# airball_sensor_board_v8.net
KiCad netlist of a schematic drawn in EAGLE
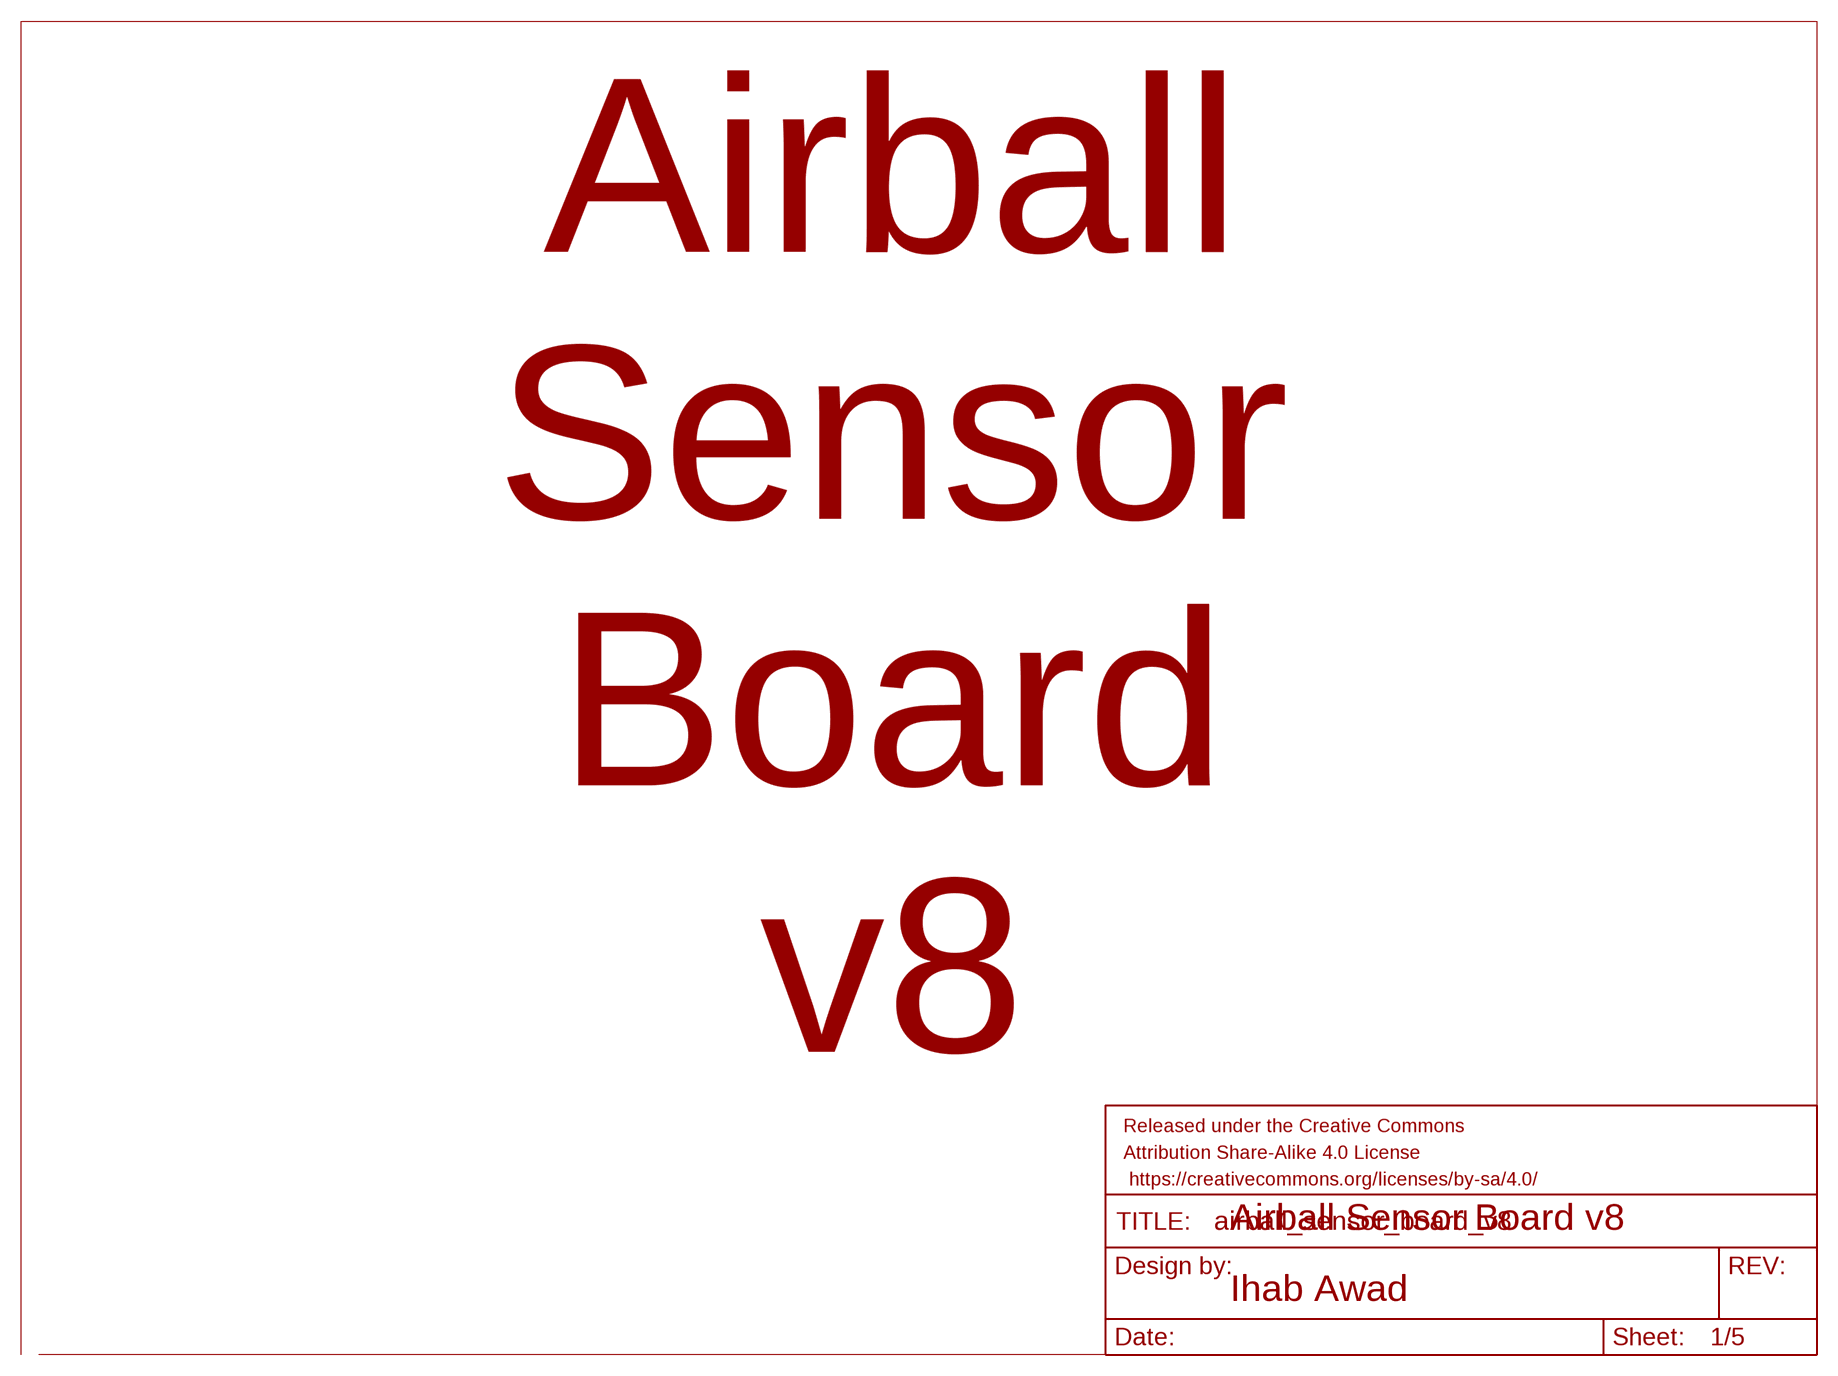
[diagram p0: schematic, sheet 1]
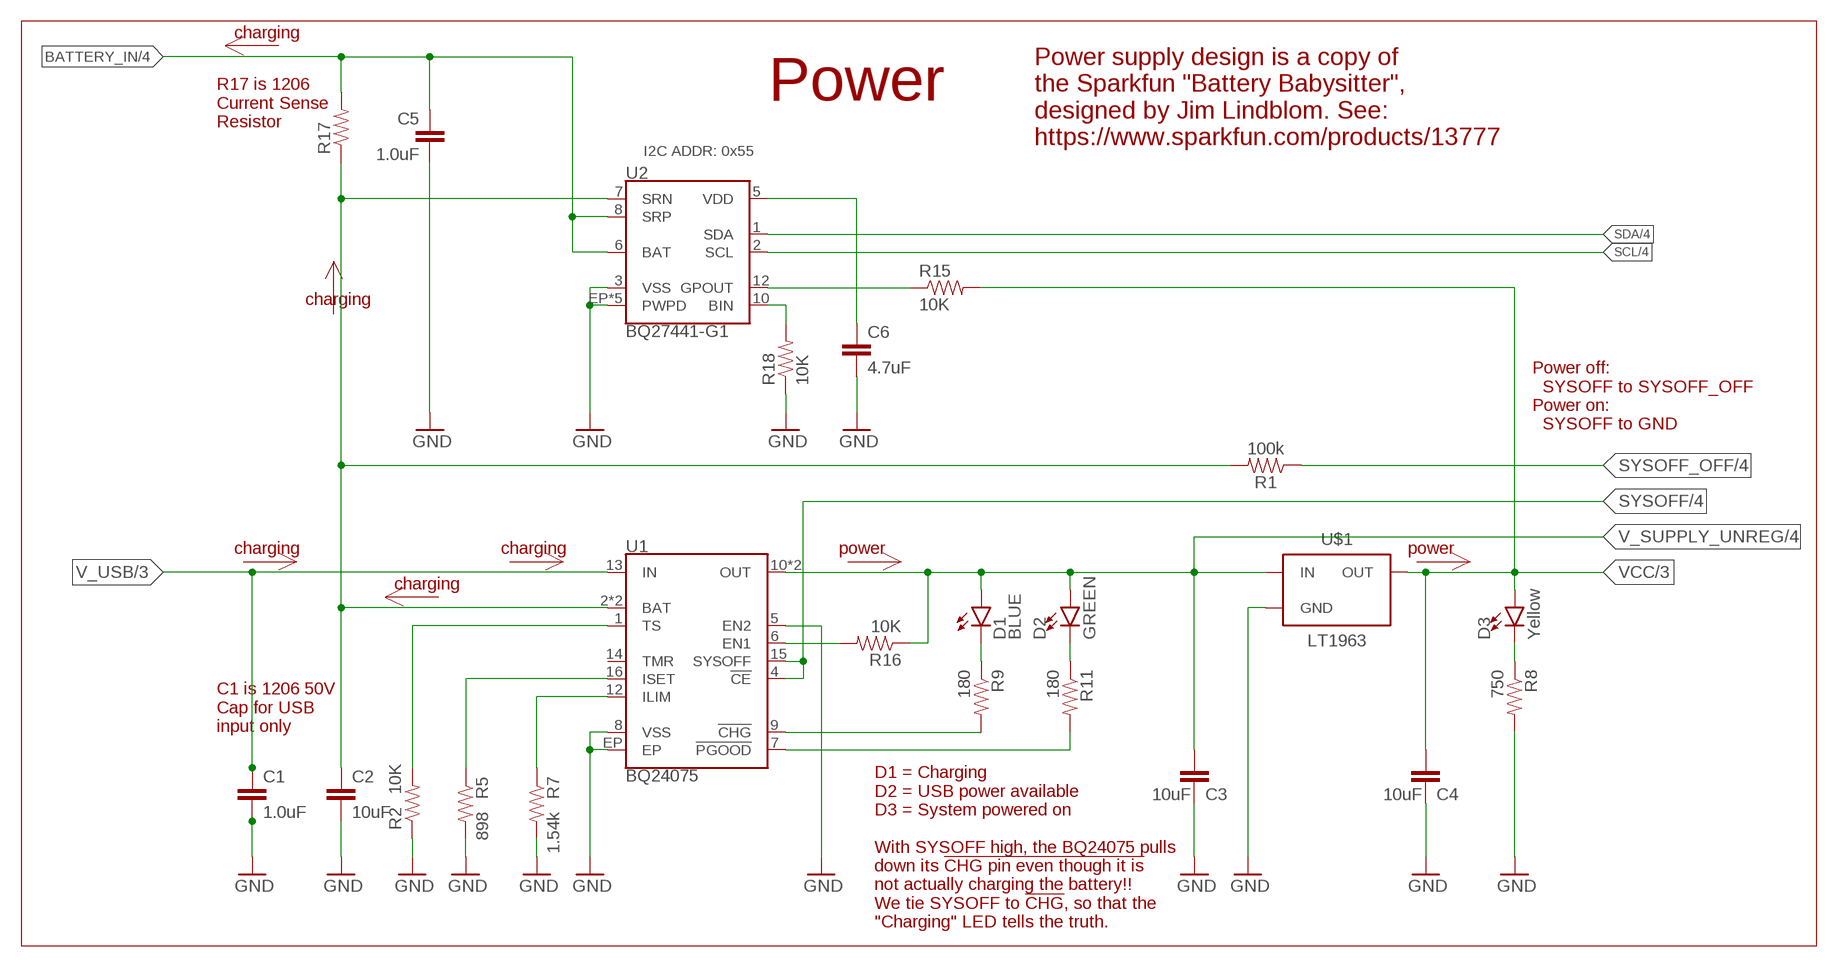
[diagram p1: schematic, sheet 2]
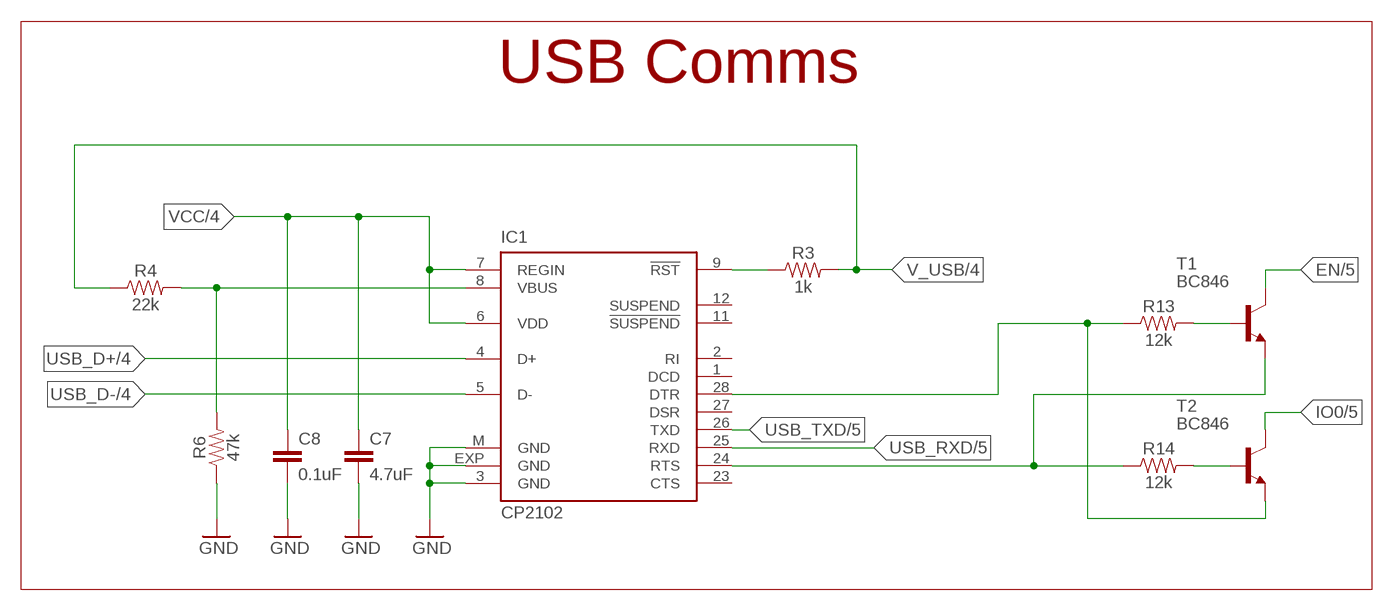
[diagram p2: schematic, sheet 3]
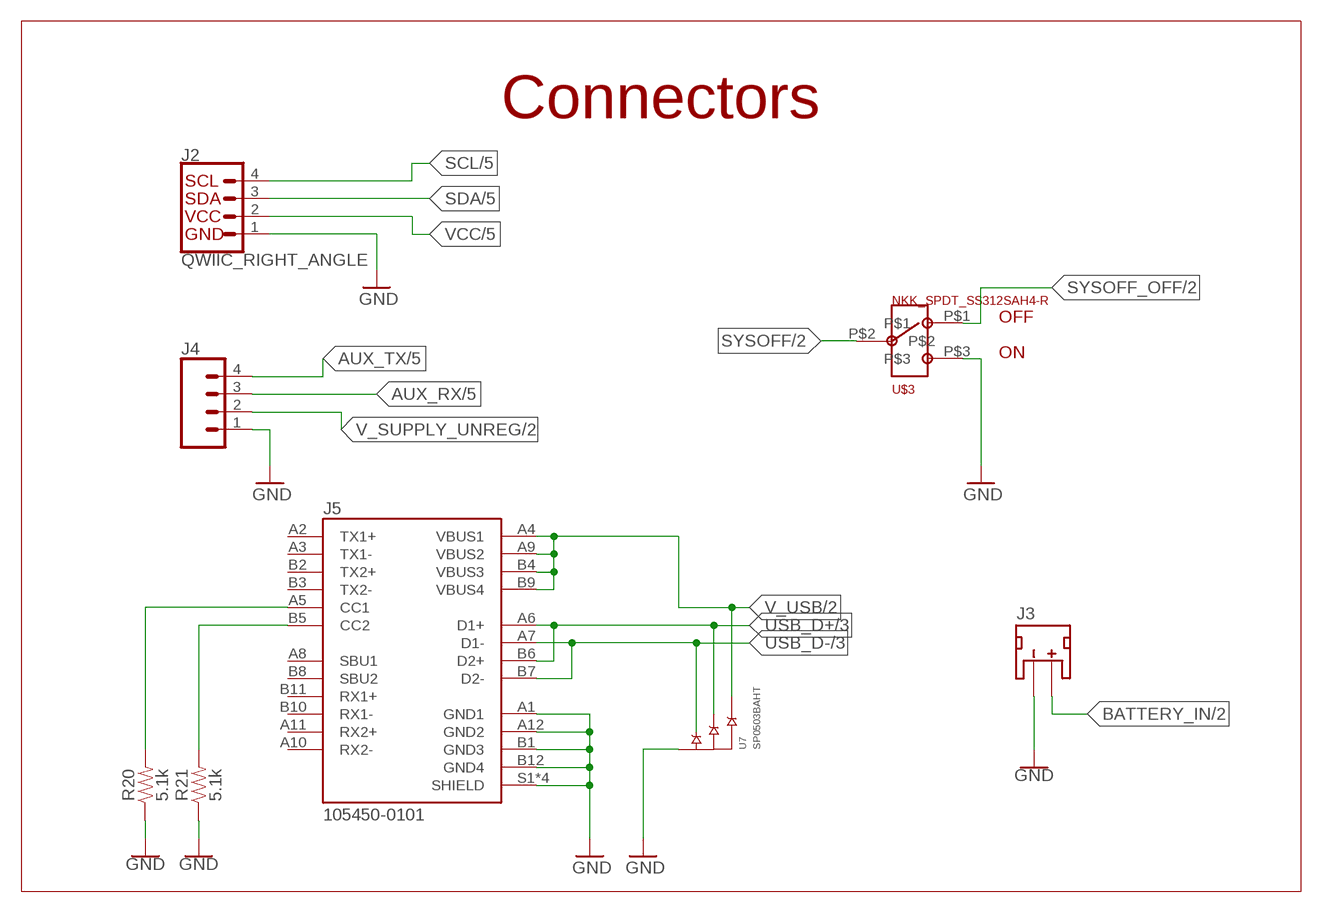
[diagram p3: schematic, sheet 4]
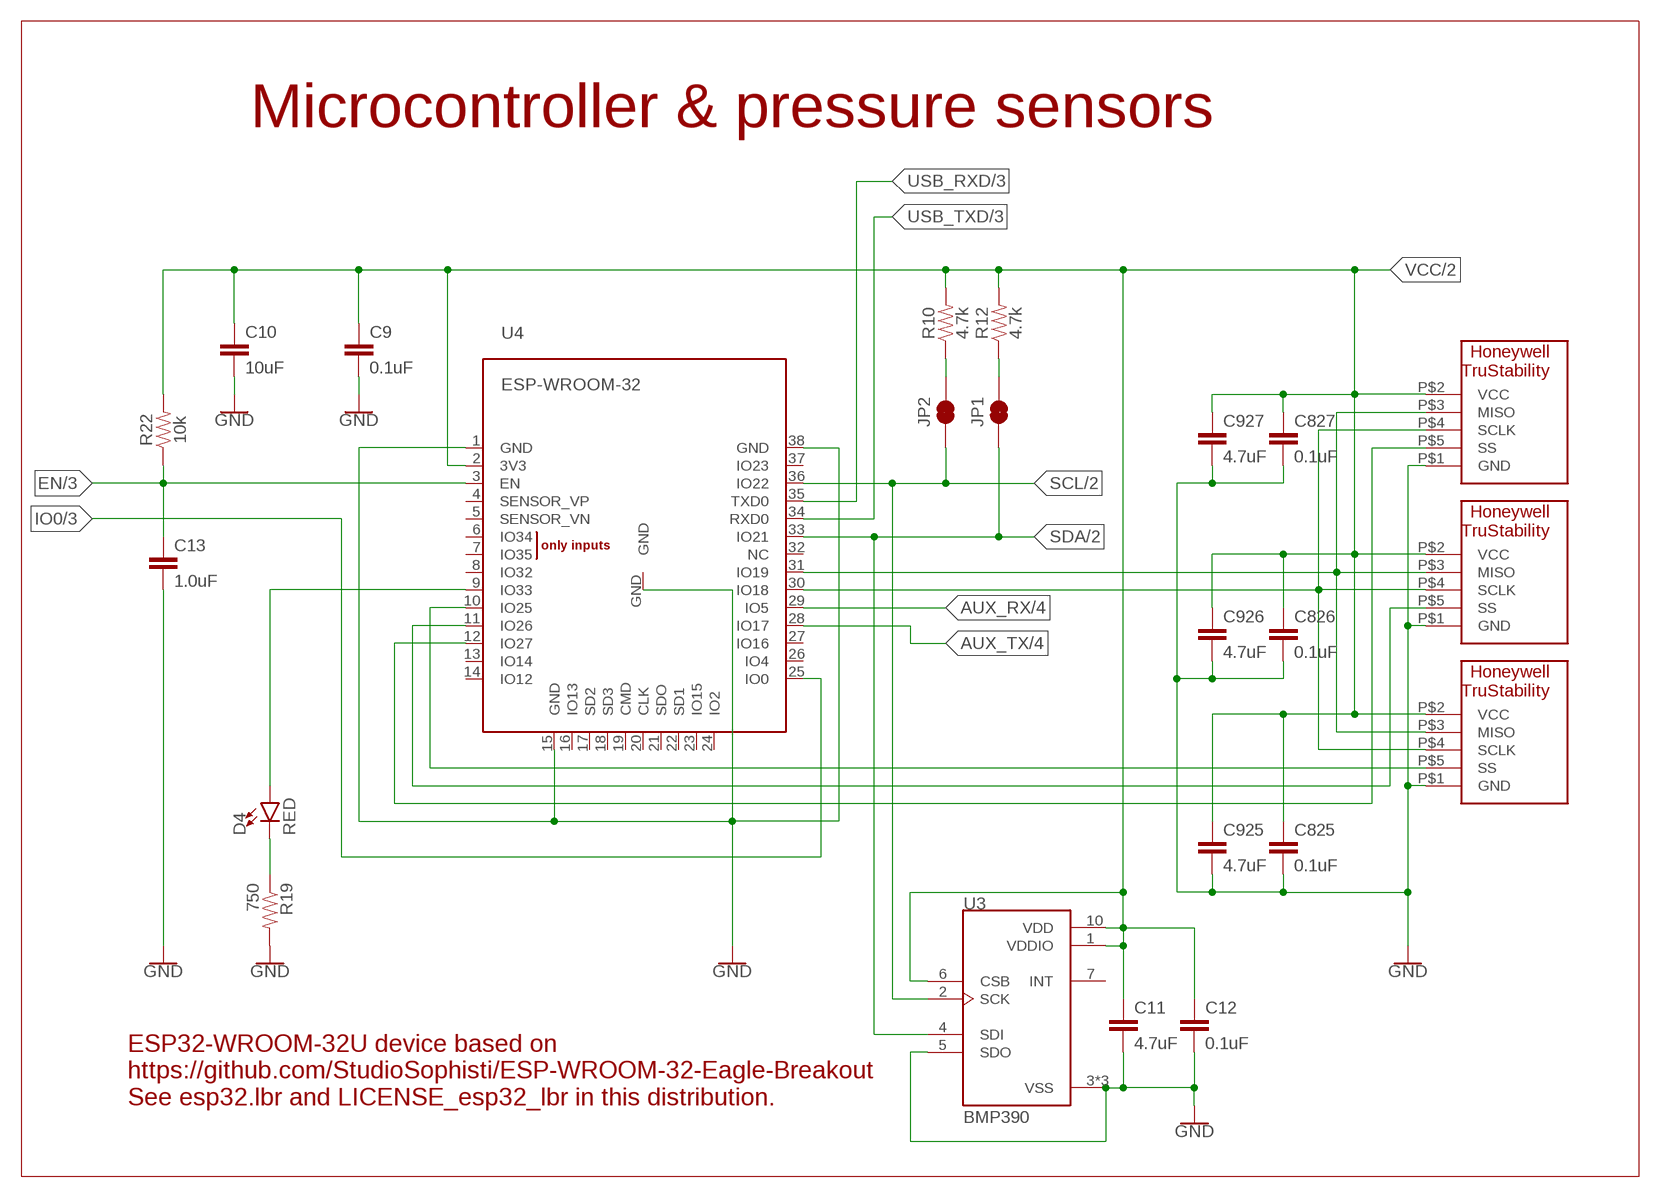
[diagram p4: schematic, sheet 5]

(export (version "E")
  (design (tool "Eeschema 10.0.6"))
  (components
    (comp (ref "C7")
      (value "4.7uF")
      (footprint "eagle-import:0603")
      (libsource (lib "eagle-import") (part "4.7UF-0603-35V-(20%)"))
    )
    (comp (ref "C8")
      (value "0.1uF")
      (footprint "eagle-import:0603")
      (libsource (lib "eagle-import") (part "0.1UF-0603-25V-(+80/-20%)"))
    )
    (comp (ref "IC1")
      (value "CP2102")
      (footprint "eagle-import:MLP28")
      (fields (field (name "MF") "FARNELL") (field (name "MPN") "CP2102-GM"))
      (libsource (lib "eagle-import") (part "CP2102"))
    )
    (comp (ref "R3")
      (value "1k")
      (footprint "eagle-import:0603")
      (libsource (lib "eagle-import") (part "1KOHM-0603-1/10W-1%"))
    )
    (comp (ref "R4")
      (value "22k")
      (footprint "eagle-import:0603")
      (libsource (lib "eagle-import") (part "22KOHM-0603-1/10W-1%"))
    )
    (comp (ref "R6")
      (value "47k")
      (footprint "eagle-import:0603")
      (libsource (lib "eagle-import") (part "47KOHM-0603-1/10W-1%"))
    )
    (comp (ref "R13")
      (value "12k")
      (footprint "eagle-import:0603")
      (libsource (lib "eagle-import") (part "12KOHM-0603-1/10W-1%"))
    )
    (comp (ref "R14")
      (value "12k")
      (footprint "eagle-import:0603")
      (libsource (lib "eagle-import") (part "12KOHM-0603-1/10W-1%"))
    )
    (comp (ref "T1")
      (value "BC846")
      (footprint "eagle-import:SOT23")
      (libsource (lib "eagle-import") (part "BC846"))
    )
    (comp (ref "T2")
      (value "BC846")
      (footprint "eagle-import:SOT23")
      (libsource (lib "eagle-import") (part "BC846"))
    )
    (comp (ref "FRAME1")
      (value "FRAME-LETTER")
      (footprint "eagle-import:CREATIVE_COMMONS")
      (libsource (lib "eagle-import") (part "FRAME-LETTER"))
    )
    (comp (ref "J2")
      (value "QWIIC_RIGHT_ANGLE")
      (footprint "eagle-import:JST04_1MM_RA")
      (libsource (lib "eagle-import") (part "QWIIC_CONNECTORJS-1MM"))
    )
    (comp (ref "J3")
      (value "JST_2MM_MALE")
      (footprint "eagle-import:JST-2-SMD")
      (libsource (lib "eagle-import") (part "JST_2MM_MALE"))
    )
    (comp (ref "J4")
      (value "CONN_04PTH")
      (footprint "eagle-import:1X04")
      (libsource (lib "eagle-import") (part "CONN_04PTH"))
    )
    (comp (ref "J5")
      (value "105450-0101")
      (footprint "eagle-import:MOLEX_105450-0101")
      (fields
        (field (name "DIGI-KEY_PART_NUMBER") "WM12856CT-ND")
        (field (name "MF") "Molex")
        (field (name "MP") "1054500101")
      )
      (libsource (lib "eagle-import") (part "105450-0101"))
    )
    (comp (ref "R20")
      (value "5.1k")
      (footprint "eagle-import:0603")
      (libsource (lib "eagle-import") (part "5.1KOHM5.1KOHM-0603-1/10W-1%"))
    )
    (comp (ref "R21")
      (value "5.1k")
      (footprint "eagle-import:0603")
      (libsource (lib "eagle-import") (part "5.1KOHM5.1KOHM-0603-1/10W-1%"))
    )
    (comp (ref "U$3")
      (value "NKK_SPDT_SS312SAH4-R")
      (footprint "eagle-import:NKK_SPDT_SS312SAH4-R")
      (libsource (lib "eagle-import") (part "NKK_SPDT_SS312SAH4-R"))
    )
    (comp (ref "U7")
      (value "SP0503BAHT")
      (footprint "eagle-import:SOT143")
      (fields (field (name "DIGI-KEY_PART_NUMBER") "F2715TR-ND") (field (name "MF") "Littelfuse Inc."))
      (libsource (lib "eagle-import") (part "SP0503BAHT"))
    )
    (comp (ref "C9")
      (value "0.1uF")
      (footprint "eagle-import:0603")
      (libsource (lib "eagle-import") (part "0.1UF-0603-25V-(+80/-20%)"))
    )
    (comp (ref "C10")
      (value "10uF")
      (footprint "eagle-import:0603")
      (libsource (lib "eagle-import") (part "10UF-0603-6.3V-20%"))
    )
    (comp (ref "C11")
      (value "4.7uF")
      (footprint "eagle-import:0603")
      (libsource (lib "eagle-import") (part "4.7UF-0603-6.3V-(10%)"))
    )
    (comp (ref "C12")
      (value "0.1uF")
      (footprint "eagle-import:0603")
      (libsource (lib "eagle-import") (part "0.1UF-0603-25V-(+80/-20%)"))
    )
    (comp (ref "C13")
      (value "1.0uF")
      (footprint "eagle-import:0603")
      (libsource (lib "eagle-import") (part "1.0UF-0603-16V-10%"))
    )
    (comp (ref "C825")
      (value "0.1uF")
      (footprint "eagle-import:0603")
      (libsource (lib "eagle-import") (part "0.1UF-0603-25V-(+80/-20%)"))
    )
    (comp (ref "C826")
      (value "0.1uF")
      (footprint "eagle-import:0603")
      (libsource (lib "eagle-import") (part "0.1UF-0603-25V-(+80/-20%)"))
    )
    (comp (ref "C827")
      (value "0.1uF")
      (footprint "eagle-import:0603")
      (libsource (lib "eagle-import") (part "0.1UF-0603-25V-(+80/-20%)"))
    )
    (comp (ref "C925")
      (value "4.7uF")
      (footprint "eagle-import:0603")
      (libsource (lib "eagle-import") (part "4.7UF-0603-6.3V-(10%)"))
    )
    (comp (ref "C926")
      (value "4.7uF")
      (footprint "eagle-import:0603")
      (libsource (lib "eagle-import") (part "4.7UF-0603-6.3V-(10%)"))
    )
    (comp (ref "C927")
      (value "4.7uF")
      (footprint "eagle-import:0603")
      (libsource (lib "eagle-import") (part "4.7UF-0603-6.3V-(10%)"))
    )
    (comp (ref "D4")
      (value "RED")
      (footprint "eagle-import:LED-0603")
      (libsource (lib "eagle-import") (part "LED-RED0603"))
    )
    (comp (ref "JP1")
      (value "JUMPER-SMT_2_NC_TRACE_SILK")
      (footprint "eagle-import:SMT-JUMPER_2_NC_TRACE_SILK")
      (libsource (lib "eagle-import") (part "JUMPER-SMT_2_NC_TRACE_SILK"))
    )
    (comp (ref "JP2")
      (value "JUMPER-SMT_2_NC_TRACE_SILK")
      (footprint "eagle-import:SMT-JUMPER_2_NC_TRACE_SILK")
      (libsource (lib "eagle-import") (part "JUMPER-SMT_2_NC_TRACE_SILK"))
    )
    (comp (ref "R10")
      (value "4.7k")
      (footprint "eagle-import:0603")
      (libsource (lib "eagle-import") (part "4.7KOHM-0603-1/10W-1%"))
    )
    (comp (ref "R12")
      (value "4.7k")
      (footprint "eagle-import:0603")
      (libsource (lib "eagle-import") (part "4.7KOHM-0603-1/10W-1%"))
    )
    (comp (ref "R19")
      (value "750")
      (footprint "eagle-import:0603-RES")
      (libsource (lib "eagle-import") (part "10KOHM-1/10W-1%(0603)0603"))
    )
    (comp (ref "R22")
      (value "10k")
      (footprint "eagle-import:0603")
      (libsource (lib "eagle-import") (part "10KOHM-0603-1/10W-1%"))
    )
    (comp (ref "U$925")
      (value "HONEYWELL_HSC_SMT")
      (footprint "eagle-import:HONEYWELL_HSC_SMT")
      (libsource (lib "eagle-import") (part "HONEYWELL_HSC_SMT"))
    )
    (comp (ref "U$926")
      (value "HONEYWELL_HSC_SMT")
      (footprint "eagle-import:HONEYWELL_HSC_SMT")
      (libsource (lib "eagle-import") (part "HONEYWELL_HSC_SMT"))
    )
    (comp (ref "U$927")
      (value "HONEYWELL_HSC_SMT")
      (footprint "eagle-import:HONEYWELL_HSC_SMT")
      (libsource (lib "eagle-import") (part "HONEYWELL_HSC_SMT"))
    )
    (comp (ref "U3")
      (value "BMP390")
      (footprint "eagle-import:PQFN50P200X200X80-10N")
      (fields (field (name "MF") "Bosch Sensortec"))
      (libsource (lib "eagle-import") (part "BMP390"))
    )
    (comp (ref "U4")
      (value "ESP-WROOM-32")
      (footprint "eagle-import:ESP-WROOM-32")
      (libsource (lib "eagle-import") (part "ESP-WROOM-32"))
    )
    (comp (ref "C1")
      (value "1.0uF")
      (footprint "eagle-import:1206-CAP")
      (libsource (lib "eagle-import") (part "1.0UF50V10%(1206)"))
    )
    (comp (ref "C2")
      (value "10uF")
      (footprint "eagle-import:0805-CAP")
      (libsource (lib "eagle-import") (part "10UF10V10%(0805)"))
    )
    (comp (ref "C3")
      (value "10uF")
      (footprint "eagle-import:0805-CAP")
      (libsource (lib "eagle-import") (part "10UF10V10%(0805)"))
    )
    (comp (ref "C4")
      (value "10uF")
      (footprint "eagle-import:0805-CAP")
      (libsource (lib "eagle-import") (part "10UF10V10%(0805)"))
    )
    (comp (ref "C5")
      (value "1.0uF")
      (footprint "eagle-import:0603-CAP")
      (libsource (lib "eagle-import") (part "1.0UF-16V-10%(0603)"))
    )
    (comp (ref "C6")
      (value "4.7uF")
      (footprint "eagle-import:0603")
      (libsource (lib "eagle-import") (part "4.7UF-0603-35V-(20%)"))
    )
    (comp (ref "D1")
      (value "BLUE")
      (footprint "eagle-import:LED-0603")
      (libsource (lib "eagle-import") (part "LED-BLUE0603"))
    )
    (comp (ref "D2")
      (value "GREEN")
      (footprint "eagle-import:LED-0603")
      (libsource (lib "eagle-import") (part "LED-GREEN0603"))
    )
    (comp (ref "D3")
      (value "Yellow")
      (footprint "eagle-import:LED-0603")
      (libsource (lib "eagle-import") (part "LED-YELLOW0603"))
    )
    (comp (ref "R1")
      (value "100k")
      (footprint "eagle-import:0603")
      (libsource (lib "eagle-import") (part "100KOHM-0603-1/10W-1%"))
    )
    (comp (ref "R2")
      (value "10K")
      (footprint "eagle-import:0603-RES")
      (libsource (lib "eagle-import") (part "10KOHM-1/10W-1%(0603)0603"))
    )
    (comp (ref "R5")
      (value "898")
      (footprint "eagle-import:0603-RES")
      (libsource (lib "eagle-import") (part "RESISTOR0603-RES"))
    )
    (comp (ref "R7")
      (value "1.54k")
      (footprint "eagle-import:0603-RES")
      (libsource (lib "eagle-import") (part "RESISTOR0603-RES"))
    )
    (comp (ref "R8")
      (value "750")
      (footprint "eagle-import:0603-RES")
      (libsource (lib "eagle-import") (part "10KOHM-1/10W-1%(0603)0603"))
    )
    (comp (ref "R9")
      (value "180")
      (footprint "eagle-import:0603-RES")
      (libsource (lib "eagle-import") (part "180OHM1/10W1%(0603)"))
    )
    (comp (ref "R11")
      (value "180")
      (footprint "eagle-import:0603-RES")
      (libsource (lib "eagle-import") (part "180OHM1/10W1%(0603)"))
    )
    (comp (ref "R15")
      (value "10K")
      (footprint "eagle-import:0603-RES")
      (libsource (lib "eagle-import") (part "10KOHM-1/10W-1%(0603)0603"))
    )
    (comp (ref "R16")
      (value "10K")
      (footprint "eagle-import:0603-RES")
      (libsource (lib "eagle-import") (part "10KOHM-1/10W-1%(0603)0603"))
    )
    (comp (ref "R17")
      (value "RESISTOR1206")
      (footprint "eagle-import:1206")
      (fields (field (name "PROD_ID") "RES-13218"))
      (libsource (lib "eagle-import") (part "SparkFun-Resistors_RESISTOR1206"))
    )
    (comp (ref "R18")
      (value "10K")
      (footprint "eagle-import:0603-RES")
      (libsource (lib "eagle-import") (part "10KOHM-1/10W-1%(0603)0603"))
    )
    (comp (ref "U$1")
      (value "LT1963")
      (footprint "eagle-import:SOT223-3")
      (libsource (lib "eagle-import") (part "LT1963"))
    )
    (comp (ref "U1")
      (value "BQ24075")
      (footprint "eagle-import:PVQFN-N16")
      (libsource (lib "eagle-import") (part "BQ24075"))
    )
    (comp (ref "U2")
      (value "BQ27441-G1")
      (footprint "eagle-import:PDSO-N12")
      (libsource (lib "eagle-import") (part "BQ27441-G1"))
    )
  )
  (nets
    (net (code "1") (name "AUX_RX") (class "Default")
      (node (ref "J4") (pin "3") (pinfunction "3_3") (pintype "passive"))
      (node (ref "U4") (pin "29") (pinfunction "IO5_29") (pintype "bidirectional"))
    )
    (net (code "2") (name "AUX_TX") (class "Default")
      (node (ref "J4") (pin "4") (pinfunction "4_4") (pintype "passive"))
      (node (ref "U4") (pin "28") (pinfunction "IO17_28") (pintype "bidirectional"))
    )
    (net (code "3") (name "BATTERY_IN") (class "Default")
      (node (ref "C5") (pin "1") (pinfunction "1_1") (pintype "passive"))
      (node (ref "J3") (pin "2") (pinfunction "+_2") (pintype "bidirectional"))
      (node (ref "R17") (pin "2") (pinfunction "2_2") (pintype "passive"))
      (node (ref "U2") (pin "6") (pinfunction "BAT_6") (pintype "bidirectional"))
      (node (ref "U2") (pin "8") (pinfunction "SRP_8") (pintype "bidirectional"))
    )
    (net (code "4") (name "EN") (class "Default")
      (node (ref "C13") (pin "1") (pinfunction "1_1") (pintype "passive"))
      (node (ref "R22") (pin "1") (pinfunction "1_1") (pintype "passive"))
      (node (ref "T1") (pin "3") (pinfunction "C_3") (pintype "passive"))
      (node (ref "U4") (pin "3") (pinfunction "EN_3") (pintype "bidirectional"))
    )
    (net (code "5") (name "GND") (class "Default")
      (node (ref "C1") (pin "2") (pinfunction "2_2") (pintype "passive"))
      (node (ref "C10") (pin "2") (pinfunction "2_2") (pintype "passive"))
      (node (ref "C11") (pin "2") (pinfunction "2_2") (pintype "passive"))
      (node (ref "C12") (pin "2") (pinfunction "2_2") (pintype "passive"))
      (node (ref "C13") (pin "2") (pinfunction "2_2") (pintype "passive"))
      (node (ref "C2") (pin "2") (pinfunction "2_2") (pintype "passive"))
      (node (ref "C3") (pin "2") (pinfunction "2_2") (pintype "passive"))
      (node (ref "C4") (pin "2") (pinfunction "2_2") (pintype "passive"))
      (node (ref "C5") (pin "2") (pinfunction "2_2") (pintype "passive"))
      (node (ref "C6") (pin "2") (pinfunction "2_2") (pintype "passive"))
      (node (ref "C7") (pin "2") (pinfunction "2_2") (pintype "passive"))
      (node (ref "C8") (pin "2") (pinfunction "2_2") (pintype "passive"))
      (node (ref "C825") (pin "2") (pinfunction "2_2") (pintype "passive"))
      (node (ref "C826") (pin "2") (pinfunction "2_2") (pintype "passive"))
      (node (ref "C827") (pin "2") (pinfunction "2_2") (pintype "passive"))
      (node (ref "C9") (pin "2") (pinfunction "2_2") (pintype "passive"))
      (node (ref "C925") (pin "2") (pinfunction "2_2") (pintype "passive"))
      (node (ref "C926") (pin "2") (pinfunction "2_2") (pintype "passive"))
      (node (ref "C927") (pin "2") (pinfunction "2_2") (pintype "passive"))
      (node (ref "IC1") (pin "3") (pinfunction "GND_3") (pintype "power_in"))
      (node (ref "IC1") (pin "EXP") (pinfunction "GND_EXP") (pintype "power_in"))
      (node (ref "IC1") (pin "M") (pinfunction "GND_M") (pintype "power_in"))
      (node (ref "J2") (pin "1") (pinfunction "1_1") (pintype "power_in"))
      (node (ref "J3") (pin "1") (pinfunction "-_1") (pintype "bidirectional"))
      (node (ref "J4") (pin "1") (pinfunction "1_1") (pintype "passive"))
      (node (ref "J5") (pin "A1") (pinfunction "GND1_A1") (pintype "passive"))
      (node (ref "J5") (pin "A12") (pinfunction "GND2_A12") (pintype "passive"))
      (node (ref "J5") (pin "B1") (pinfunction "GND3_B1") (pintype "passive"))
      (node (ref "J5") (pin "B12") (pinfunction "GND4_B12") (pintype "passive"))
      (node (ref "J5") (pin "S1") (pinfunction "SHIELD_S1") (pintype "passive"))
      (node (ref "J5") (pin "S2") (pinfunction "SHIELD_S2") (pintype "passive"))
      (node (ref "J5") (pin "S3") (pinfunction "SHIELD_S3") (pintype "passive"))
      (node (ref "J5") (pin "S4") (pinfunction "SHIELD_S4") (pintype "passive"))
      (node (ref "R18") (pin "1") (pinfunction "1_1") (pintype "passive"))
      (node (ref "R19") (pin "2") (pinfunction "2_2") (pintype "passive"))
      (node (ref "R2") (pin "1") (pinfunction "1_1") (pintype "passive"))
      (node (ref "R20") (pin "1") (pinfunction "1_1") (pintype "passive"))
      (node (ref "R21") (pin "1") (pinfunction "1_1") (pintype "passive"))
      (node (ref "R5") (pin "2") (pinfunction "2_2") (pintype "passive"))
      (node (ref "R6") (pin "1") (pinfunction "1_1") (pintype "passive"))
      (node (ref "R7") (pin "2") (pinfunction "2_2") (pintype "passive"))
      (node (ref "R8") (pin "2") (pinfunction "2_2") (pintype "passive"))
      (node (ref "U$1") (pin "2") (pinfunction "GND_2") (pintype "power_in"))
      (node (ref "U$1") (pin "TAB") (pinfunction "GND_TAB") (pintype "power_in"))
      (node (ref "U$3") (pin "P$3") (pinfunction "P$3_P$3") (pintype "bidirectional"))
      (node (ref "U$925") (pin "P$1") (pinfunction "GND_P$1") (pintype "bidirectional"))
      (node (ref "U$926") (pin "P$1") (pinfunction "GND_P$1") (pintype "bidirectional"))
      (node (ref "U$927") (pin "P$1") (pinfunction "GND_P$1") (pintype "bidirectional"))
      (node (ref "U1") (pin "5") (pinfunction "EN2_5") (pintype "bidirectional"))
      (node (ref "U1") (pin "8") (pinfunction "VSS_8") (pintype "bidirectional"))
      (node (ref "U1") (pin "EP") (pinfunction "EP_EP") (pintype "bidirectional"))
      (node (ref "U2") (pin "3") (pinfunction "VSS_3") (pintype "bidirectional"))
      (node (ref "U2") (pin "EP") (pinfunction "PWPD_EP") (pintype "bidirectional"))
      (node (ref "U2") (pin "EP1") (pinfunction "PWPD_EP1") (pintype "bidirectional"))
      (node (ref "U2") (pin "EP2") (pinfunction "PWPD_EP2") (pintype "bidirectional"))
      (node (ref "U2") (pin "EP3") (pinfunction "PWPD_EP3") (pintype "bidirectional"))
      (node (ref "U2") (pin "EP4") (pinfunction "PWPD_EP4") (pintype "bidirectional"))
      (node (ref "U3") (pin "3") (pinfunction "VSS_3") (pintype "power_in"))
      (node (ref "U3") (pin "5") (pinfunction "SDO_5") (pintype "bidirectional"))
      (node (ref "U3") (pin "8") (pinfunction "VSS_8") (pintype "power_in"))
      (node (ref "U3") (pin "9") (pinfunction "VSS_9") (pintype "power_in"))
      (node (ref "U4") (pin "1") (pinfunction "GND_1") (pintype "bidirectional"))
      (node (ref "U4") (pin "15") (pinfunction "GND_15") (pintype "bidirectional"))
      (node (ref "U4") (pin "38") (pinfunction "GND_38") (pintype "bidirectional"))
      (node (ref "U4") (pin "GND") (pinfunction "GND_GND") (pintype "bidirectional"))
      (node (ref "U7") (pin "1") (pinfunction "GND_1") (pintype "bidirectional"))
    )
    (net (code "6") (name "IO0") (class "Default")
      (node (ref "T2") (pin "3") (pinfunction "C_3") (pintype "passive"))
      (node (ref "U4") (pin "25") (pinfunction "IO0_25") (pintype "bidirectional"))
    )
    (net (code "7") (name "Net-(D1-PadC)") (class "Default")
      (node (ref "D1") (pin "C") (pinfunction "C_C") (pintype "passive"))
      (node (ref "R9") (pin "1") (pinfunction "1_1") (pintype "passive"))
    )
    (net (code "8") (name "Net-(D2-PadC)") (class "Default")
      (node (ref "D2") (pin "C") (pinfunction "C_C") (pintype "passive"))
      (node (ref "R11") (pin "1") (pinfunction "1_1") (pintype "passive"))
    )
    (net (code "9") (name "Net-(D3-PadC)") (class "Default")
      (node (ref "D3") (pin "C") (pinfunction "C_C") (pintype "passive"))
      (node (ref "R8") (pin "1") (pinfunction "1_1") (pintype "passive"))
    )
    (net (code "10") (name "Net-(D4-PadC)") (class "Default")
      (node (ref "D4") (pin "C") (pinfunction "C_C") (pintype "passive"))
      (node (ref "R19") (pin "1") (pinfunction "1_1") (pintype "passive"))
    )
    (net (code "11") (name "Net-(IC1-DTR)") (class "Default")
      (node (ref "IC1") (pin "28") (pinfunction "DTR_28") (pintype "output"))
      (node (ref "R13") (pin "1") (pinfunction "1_1") (pintype "passive"))
      (node (ref "T2") (pin "2") (pinfunction "E_2") (pintype "passive"))
    )
    (net (code "12") (name "Net-(IC1-RTS)") (class "Default")
      (node (ref "IC1") (pin "24") (pinfunction "RTS_24") (pintype "output"))
      (node (ref "R14") (pin "1") (pinfunction "1_1") (pintype "passive"))
      (node (ref "T1") (pin "2") (pinfunction "E_2") (pintype "passive"))
    )
    (net (code "13") (name "Net-(IC1-VBUS)") (class "Default")
      (node (ref "IC1") (pin "8") (pinfunction "VBUS_8") (pintype "input"))
      (node (ref "R4") (pin "2") (pinfunction "2_2") (pintype "passive"))
      (node (ref "R6") (pin "2") (pinfunction "2_2") (pintype "passive"))
    )
    (net (code "14") (name "Net-(IC1-~{RST})") (class "Default")
      (node (ref "IC1") (pin "9") (pinfunction "~{RST}_9") (pintype "bidirectional"))
      (node (ref "R3") (pin "1") (pinfunction "1_1") (pintype "passive"))
    )
    (net (code "15") (name "Net-(J5-CC1)") (class "Default")
      (node (ref "J5") (pin "A5") (pinfunction "CC1_A5") (pintype "passive"))
      (node (ref "R20") (pin "2") (pinfunction "2_2") (pintype "passive"))
    )
    (net (code "16") (name "Net-(J5-CC2)") (class "Default")
      (node (ref "J5") (pin "B5") (pinfunction "CC2_B5") (pintype "passive"))
      (node (ref "R21") (pin "2") (pinfunction "2_2") (pintype "passive"))
    )
    (net (code "17") (name "Net-(JP1-Pad2)") (class "Default")
      (node (ref "JP1") (pin "2") (pinfunction "2_2") (pintype "passive"))
      (node (ref "R12") (pin "1") (pinfunction "1_1") (pintype "passive"))
    )
    (net (code "18") (name "Net-(JP2-Pad2)") (class "Default")
      (node (ref "JP2") (pin "2") (pinfunction "2_2") (pintype "passive"))
      (node (ref "R10") (pin "1") (pinfunction "1_1") (pintype "passive"))
    )
    (net (code "19") (name "Net-(T1-B)") (class "Default")
      (node (ref "R13") (pin "2") (pinfunction "2_2") (pintype "passive"))
      (node (ref "T1") (pin "1") (pinfunction "B_1") (pintype "passive"))
    )
    (net (code "20") (name "Net-(T2-B)") (class "Default")
      (node (ref "R14") (pin "2") (pinfunction "2_2") (pintype "passive"))
      (node (ref "T2") (pin "1") (pinfunction "B_1") (pintype "passive"))
    )
    (net (code "21") (name "Net-(U$925-MISO)") (class "Default")
      (node (ref "U$925") (pin "P$3") (pinfunction "MISO_P$3") (pintype "bidirectional"))
      (node (ref "U$926") (pin "P$3") (pinfunction "MISO_P$3") (pintype "bidirectional"))
      (node (ref "U$927") (pin "P$3") (pinfunction "MISO_P$3") (pintype "bidirectional"))
      (node (ref "U4") (pin "31") (pinfunction "IO19_31") (pintype "bidirectional"))
    )
    (net (code "22") (name "Net-(U$925-SCLK)") (class "Default")
      (node (ref "U$925") (pin "P$4") (pinfunction "SCLK_P$4") (pintype "bidirectional"))
      (node (ref "U$926") (pin "P$4") (pinfunction "SCLK_P$4") (pintype "bidirectional"))
      (node (ref "U$927") (pin "P$4") (pinfunction "SCLK_P$4") (pintype "bidirectional"))
      (node (ref "U4") (pin "30") (pinfunction "IO18_30") (pintype "bidirectional"))
    )
    (net (code "23") (name "Net-(U$925-SS)") (class "Default")
      (node (ref "U$925") (pin "P$5") (pinfunction "SS_P$5") (pintype "bidirectional"))
      (node (ref "U4") (pin "10") (pinfunction "IO25_10") (pintype "bidirectional"))
    )
    (net (code "24") (name "Net-(U$926-SS)") (class "Default")
      (node (ref "U$926") (pin "P$5") (pinfunction "SS_P$5") (pintype "bidirectional"))
      (node (ref "U4") (pin "11") (pinfunction "IO26_11") (pintype "bidirectional"))
    )
    (net (code "25") (name "Net-(U$927-SS)") (class "Default")
      (node (ref "U$927") (pin "P$5") (pinfunction "SS_P$5") (pintype "bidirectional"))
      (node (ref "U4") (pin "12") (pinfunction "IO27_12") (pintype "bidirectional"))
    )
    (net (code "26") (name "Net-(U1-EN1)") (class "Default")
      (node (ref "R16") (pin "2") (pinfunction "2_2") (pintype "passive"))
      (node (ref "U1") (pin "6") (pinfunction "EN1_6") (pintype "bidirectional"))
    )
    (net (code "27") (name "Net-(U1-ILIM)") (class "Default")
      (node (ref "R7") (pin "1") (pinfunction "1_1") (pintype "passive"))
      (node (ref "U1") (pin "12") (pinfunction "ILIM_12") (pintype "bidirectional"))
    )
    (net (code "28") (name "Net-(U1-ISET)") (class "Default")
      (node (ref "R5") (pin "1") (pinfunction "1_1") (pintype "passive"))
      (node (ref "U1") (pin "16") (pinfunction "ISET_16") (pintype "bidirectional"))
    )
    (net (code "29") (name "Net-(U1-TS)") (class "Default")
      (node (ref "R2") (pin "2") (pinfunction "2_2") (pintype "passive"))
      (node (ref "U1") (pin "1") (pinfunction "TS_1") (pintype "bidirectional"))
    )
    (net (code "30") (name "Net-(U1-~{CHG})") (class "Default")
      (node (ref "R9") (pin "2") (pinfunction "2_2") (pintype "passive"))
      (node (ref "U1") (pin "9") (pinfunction "~{CHG}_9") (pintype "bidirectional"))
    )
    (net (code "31") (name "Net-(U1-~{PGOOD})") (class "Default")
      (node (ref "R11") (pin "2") (pinfunction "2_2") (pintype "passive"))
      (node (ref "U1") (pin "7") (pinfunction "~{PGOOD}_7") (pintype "bidirectional"))
    )
    (net (code "32") (name "Net-(U2-BIN)") (class "Default")
      (node (ref "R18") (pin "2") (pinfunction "2_2") (pintype "passive"))
      (node (ref "U2") (pin "10") (pinfunction "BIN_10") (pintype "bidirectional"))
    )
    (net (code "33") (name "Net-(U2-GPOUT)") (class "Default")
      (node (ref "R15") (pin "1") (pinfunction "1_1") (pintype "passive"))
      (node (ref "U2") (pin "12") (pinfunction "GPOUT_12") (pintype "bidirectional"))
    )
    (net (code "34") (name "Net-(U2-SRN)") (class "Default")
      (node (ref "C2") (pin "1") (pinfunction "1_1") (pintype "passive"))
      (node (ref "R1") (pin "2") (pinfunction "2_2") (pintype "passive"))
      (node (ref "R17") (pin "1") (pinfunction "1_1") (pintype "passive"))
      (node (ref "U1") (pin "2") (pinfunction "BAT_2") (pintype "bidirectional"))
      (node (ref "U1") (pin "3") (pinfunction "BAT_3") (pintype "bidirectional"))
      (node (ref "U2") (pin "7") (pinfunction "SRN_7") (pintype "bidirectional"))
    )
    (net (code "35") (name "Net-(U2-VDD)") (class "Default")
      (node (ref "C6") (pin "1") (pinfunction "1_1") (pintype "passive"))
      (node (ref "U2") (pin "5") (pinfunction "VDD_5") (pintype "bidirectional"))
    )
    (net (code "36") (name "Net-(U4-IO33)") (class "Default")
      (node (ref "D4") (pin "A") (pinfunction "A_A") (pintype "passive"))
      (node (ref "U4") (pin "9") (pinfunction "IO33_9") (pintype "bidirectional"))
    )
    (net (code "37") (name "SCL") (class "Default")
      (node (ref "J2") (pin "4") (pinfunction "4_4") (pintype "passive"))
      (node (ref "JP2") (pin "1") (pinfunction "1_1") (pintype "passive"))
      (node (ref "U2") (pin "2") (pinfunction "SCL_2") (pintype "bidirectional"))
      (node (ref "U3") (pin "2") (pinfunction "SCK_2") (pintype "input"))
      (node (ref "U4") (pin "36") (pinfunction "IO22_36") (pintype "bidirectional"))
    )
    (net (code "38") (name "SDA") (class "Default")
      (node (ref "J2") (pin "3") (pinfunction "3_3") (pintype "passive"))
      (node (ref "JP1") (pin "1") (pinfunction "1_1") (pintype "passive"))
      (node (ref "U2") (pin "1") (pinfunction "SDA_1") (pintype "bidirectional"))
      (node (ref "U3") (pin "4") (pinfunction "SDI_4") (pintype "bidirectional"))
      (node (ref "U4") (pin "33") (pinfunction "IO21_33") (pintype "bidirectional"))
    )
    (net (code "39") (name "SYSOFF") (class "Default")
      (node (ref "U$3") (pin "P$2") (pinfunction "P$2_P$2") (pintype "bidirectional"))
      (node (ref "U1") (pin "15") (pinfunction "SYSOFF_15") (pintype "bidirectional"))
      (node (ref "U1") (pin "4") (pinfunction "~{CE}_4") (pintype "bidirectional"))
    )
    (net (code "40") (name "SYSOFF_OFF") (class "Default")
      (node (ref "R1") (pin "1") (pinfunction "1_1") (pintype "passive"))
      (node (ref "U$3") (pin "P$1") (pinfunction "P$1_P$1") (pintype "bidirectional"))
    )
    (net (code "41") (name "USB_D+") (class "Default")
      (node (ref "IC1") (pin "4") (pinfunction "D+_4") (pintype "bidirectional"))
      (node (ref "J5") (pin "A6") (pinfunction "D1+_A6") (pintype "passive"))
      (node (ref "J5") (pin "B6") (pinfunction "D2+_B6") (pintype "passive"))
      (node (ref "U7") (pin "3") (pinfunction "B_3") (pintype "bidirectional"))
    )
    (net (code "42") (name "USB_D-") (class "Default")
      (node (ref "IC1") (pin "5") (pinfunction "D-_5") (pintype "bidirectional"))
      (node (ref "J5") (pin "A7") (pinfunction "D1-_A7") (pintype "passive"))
      (node (ref "J5") (pin "B7") (pinfunction "D2-_B7") (pintype "passive"))
      (node (ref "U7") (pin "2") (pinfunction "A_2") (pintype "bidirectional"))
    )
    (net (code "43") (name "USB_RXD") (class "Default")
      (node (ref "IC1") (pin "25") (pinfunction "RXD_25") (pintype "input"))
      (node (ref "U4") (pin "35") (pinfunction "TXD0_35") (pintype "bidirectional"))
    )
    (net (code "44") (name "USB_TXD") (class "Default")
      (node (ref "IC1") (pin "26") (pinfunction "TXD_26") (pintype "output"))
      (node (ref "U4") (pin "34") (pinfunction "RXD0_34") (pintype "bidirectional"))
    )
    (net (code "45") (name "VCC") (class "Default")
      (node (ref "C10") (pin "1") (pinfunction "1_1") (pintype "passive"))
      (node (ref "C11") (pin "1") (pinfunction "1_1") (pintype "passive"))
      (node (ref "C12") (pin "1") (pinfunction "1_1") (pintype "passive"))
      (node (ref "C4") (pin "1") (pinfunction "1_1") (pintype "passive"))
      (node (ref "C7") (pin "1") (pinfunction "1_1") (pintype "passive"))
      (node (ref "C8") (pin "1") (pinfunction "1_1") (pintype "passive"))
      (node (ref "C825") (pin "1") (pinfunction "1_1") (pintype "passive"))
      (node (ref "C826") (pin "1") (pinfunction "1_1") (pintype "passive"))
      (node (ref "C827") (pin "1") (pinfunction "1_1") (pintype "passive"))
      (node (ref "C9") (pin "1") (pinfunction "1_1") (pintype "passive"))
      (node (ref "C925") (pin "1") (pinfunction "1_1") (pintype "passive"))
      (node (ref "C926") (pin "1") (pinfunction "1_1") (pintype "passive"))
      (node (ref "C927") (pin "1") (pinfunction "1_1") (pintype "passive"))
      (node (ref "D3") (pin "A") (pinfunction "A_A") (pintype "passive"))
      (node (ref "IC1") (pin "6") (pinfunction "VDD_6") (pintype "power_in"))
      (node (ref "IC1") (pin "7") (pinfunction "REGIN_7") (pintype "passive"))
      (node (ref "J2") (pin "2") (pinfunction "2_2") (pintype "power_in"))
      (node (ref "R10") (pin "2") (pinfunction "2_2") (pintype "passive"))
      (node (ref "R12") (pin "2") (pinfunction "2_2") (pintype "passive"))
      (node (ref "R15") (pin "2") (pinfunction "2_2") (pintype "passive"))
      (node (ref "R22") (pin "2") (pinfunction "2_2") (pintype "passive"))
      (node (ref "U$1") (pin "3") (pinfunction "OUT_3") (pintype "power_in"))
      (node (ref "U$925") (pin "P$2") (pinfunction "VCC_P$2") (pintype "bidirectional"))
      (node (ref "U$926") (pin "P$2") (pinfunction "VCC_P$2") (pintype "bidirectional"))
      (node (ref "U$927") (pin "P$2") (pinfunction "VCC_P$2") (pintype "bidirectional"))
      (node (ref "U3") (pin "1") (pinfunction "VDDIO_1") (pintype "power_in"))
      (node (ref "U3") (pin "10") (pinfunction "VDD_10") (pintype "power_in"))
      (node (ref "U3") (pin "6") (pinfunction "CSB_6") (pintype "input"))
      (node (ref "U4") (pin "2") (pinfunction "3V3_2") (pintype "bidirectional"))
    )
    (net (code "46") (name "V_SUPPLY_UNREG") (class "Default")
      (node (ref "C3") (pin "1") (pinfunction "1_1") (pintype "passive"))
      (node (ref "D1") (pin "A") (pinfunction "A_A") (pintype "passive"))
      (node (ref "D2") (pin "A") (pinfunction "A_A") (pintype "passive"))
      (node (ref "J4") (pin "2") (pinfunction "2_2") (pintype "passive"))
      (node (ref "R16") (pin "1") (pinfunction "1_1") (pintype "passive"))
      (node (ref "U$1") (pin "1") (pinfunction "IN_1") (pintype "power_in"))
      (node (ref "U1") (pin "10") (pinfunction "OUT_10") (pintype "bidirectional"))
      (node (ref "U1") (pin "11") (pinfunction "OUT_11") (pintype "bidirectional"))
    )
    (net (code "47") (name "V_USB") (class "Default")
      (node (ref "C1") (pin "1") (pinfunction "1_1") (pintype "passive"))
      (node (ref "J5") (pin "A4") (pinfunction "VBUS1_A4") (pintype "passive"))
      (node (ref "J5") (pin "A9") (pinfunction "VBUS2_A9") (pintype "passive"))
      (node (ref "J5") (pin "B4") (pinfunction "VBUS3_B4") (pintype "passive"))
      (node (ref "J5") (pin "B9") (pinfunction "VBUS4_B9") (pintype "passive"))
      (node (ref "R3") (pin "2") (pinfunction "2_2") (pintype "passive"))
      (node (ref "R4") (pin "1") (pinfunction "1_1") (pintype "passive"))
      (node (ref "U1") (pin "13") (pinfunction "IN_13") (pintype "bidirectional"))
      (node (ref "U7") (pin "4") (pinfunction "C_4") (pintype "bidirectional"))
    )
    (net (code "48") (name "unconnected-(IC1-CTS-Pad23)") (class "Default")
      (node (ref "IC1") (pin "23") (pinfunction "CTS_23") (pintype "input"))
    )
    (net (code "49") (name "unconnected-(IC1-DCD-Pad1)") (class "Default")
      (node (ref "IC1") (pin "1") (pinfunction "DCD_1") (pintype "input"))
    )
    (net (code "50") (name "unconnected-(IC1-DSR-Pad27)") (class "Default")
      (node (ref "IC1") (pin "27") (pinfunction "DSR_27") (pintype "input"))
    )
    (net (code "51") (name "unconnected-(IC1-RI-Pad2)") (class "Default")
      (node (ref "IC1") (pin "2") (pinfunction "RI_2") (pintype "input"))
    )
    (net (code "52") (name "unconnected-(IC1-SUSPEND-Pad12)") (class "Default")
      (node (ref "IC1") (pin "12") (pinfunction "SUSPEND_12") (pintype "output"))
    )
    (net (code "53") (name "unconnected-(IC1-~{SUSPEND}-Pad11)") (class "Default")
      (node (ref "IC1") (pin "11") (pinfunction "~{SUSPEND}_11") (pintype "output"))
    )
    (net (code "54") (name "unconnected-(J3-PAD1-PadNC1)") (class "Default")
      (node (ref "J3") (pin "NC1") (pinfunction "PAD1_NC1") (pintype "bidirectional"))
    )
    (net (code "55") (name "unconnected-(J3-PAD2-PadNC2)") (class "Default")
      (node (ref "J3") (pin "NC2") (pinfunction "PAD2_NC2") (pintype "bidirectional"))
    )
    (net (code "56") (name "unconnected-(J5-RX1+-PadB11)") (class "Default")
      (node (ref "J5") (pin "B11") (pinfunction "RX1+_B11") (pintype "passive"))
    )
    (net (code "57") (name "unconnected-(J5-RX1--PadB10)") (class "Default")
      (node (ref "J5") (pin "B10") (pinfunction "RX1-_B10") (pintype "passive"))
    )
    (net (code "58") (name "unconnected-(J5-RX2+-PadA11)") (class "Default")
      (node (ref "J5") (pin "A11") (pinfunction "RX2+_A11") (pintype "passive"))
    )
    (net (code "59") (name "unconnected-(J5-RX2--PadA10)") (class "Default")
      (node (ref "J5") (pin "A10") (pinfunction "RX2-_A10") (pintype "passive"))
    )
    (net (code "60") (name "unconnected-(J5-SBU1-PadA8)") (class "Default")
      (node (ref "J5") (pin "A8") (pinfunction "SBU1_A8") (pintype "passive"))
    )
    (net (code "61") (name "unconnected-(J5-SBU2-PadB8)") (class "Default")
      (node (ref "J5") (pin "B8") (pinfunction "SBU2_B8") (pintype "passive"))
    )
    (net (code "62") (name "unconnected-(J5-TX1+-PadA2)") (class "Default")
      (node (ref "J5") (pin "A2") (pinfunction "TX1+_A2") (pintype "passive"))
    )
    (net (code "63") (name "unconnected-(J5-TX1--PadA3)") (class "Default")
      (node (ref "J5") (pin "A3") (pinfunction "TX1-_A3") (pintype "passive"))
    )
    (net (code "64") (name "unconnected-(J5-TX2+-PadB2)") (class "Default")
      (node (ref "J5") (pin "B2") (pinfunction "TX2+_B2") (pintype "passive"))
    )
    (net (code "65") (name "unconnected-(J5-TX2--PadB3)") (class "Default")
      (node (ref "J5") (pin "B3") (pinfunction "TX2-_B3") (pintype "passive"))
    )
    (net (code "66") (name "unconnected-(U1-TMR-Pad14)") (class "Default")
      (node (ref "U1") (pin "14") (pinfunction "TMR_14") (pintype "bidirectional"))
    )
    (net (code "67") (name "unconnected-(U3-INT-Pad7)") (class "Default")
      (node (ref "U3") (pin "7") (pinfunction "INT_7") (pintype "output"))
    )
    (net (code "68") (name "unconnected-(U4-CLK-Pad20)") (class "Default")
      (node (ref "U4") (pin "20") (pinfunction "CLK_20") (pintype "bidirectional"))
    )
    (net (code "69") (name "unconnected-(U4-CMD-Pad19)") (class "Default")
      (node (ref "U4") (pin "19") (pinfunction "CMD_19") (pintype "bidirectional"))
    )
    (net (code "70") (name "unconnected-(U4-IO2-Pad24)") (class "Default")
      (node (ref "U4") (pin "24") (pinfunction "IO2_24") (pintype "bidirectional"))
    )
    (net (code "71") (name "unconnected-(U4-IO4-Pad26)") (class "Default")
      (node (ref "U4") (pin "26") (pinfunction "IO4_26") (pintype "bidirectional"))
    )
    (net (code "72") (name "unconnected-(U4-IO12-Pad14)") (class "Default")
      (node (ref "U4") (pin "14") (pinfunction "IO12_14") (pintype "bidirectional"))
    )
    (net (code "73") (name "unconnected-(U4-IO13-Pad16)") (class "Default")
      (node (ref "U4") (pin "16") (pinfunction "IO13_16") (pintype "bidirectional"))
    )
    (net (code "74") (name "unconnected-(U4-IO14-Pad13)") (class "Default")
      (node (ref "U4") (pin "13") (pinfunction "IO14_13") (pintype "bidirectional"))
    )
    (net (code "75") (name "unconnected-(U4-IO15-Pad23)") (class "Default")
      (node (ref "U4") (pin "23") (pinfunction "IO15_23") (pintype "bidirectional"))
    )
    (net (code "76") (name "unconnected-(U4-IO16-Pad27)") (class "Default")
      (node (ref "U4") (pin "27") (pinfunction "IO16_27") (pintype "bidirectional"))
    )
    (net (code "77") (name "unconnected-(U4-IO23-Pad37)") (class "Default")
      (node (ref "U4") (pin "37") (pinfunction "IO23_37") (pintype "bidirectional"))
    )
    (net (code "78") (name "unconnected-(U4-IO32-Pad8)") (class "Default")
      (node (ref "U4") (pin "8") (pinfunction "IO32_8") (pintype "bidirectional"))
    )
    (net (code "79") (name "unconnected-(U4-IO34-Pad6)") (class "Default")
      (node (ref "U4") (pin "6") (pinfunction "IO34_6") (pintype "input"))
    )
    (net (code "80") (name "unconnected-(U4-IO35-Pad7)") (class "Default")
      (node (ref "U4") (pin "7") (pinfunction "IO35_7") (pintype "input"))
    )
    (net (code "81") (name "unconnected-(U4-NC-Pad32)") (class "Default")
      (node (ref "U4") (pin "32") (pinfunction "NC_32") (pintype "bidirectional"))
    )
    (net (code "82") (name "unconnected-(U4-SD1-Pad22)") (class "Default")
      (node (ref "U4") (pin "22") (pinfunction "SD1_22") (pintype "bidirectional"))
    )
    (net (code "83") (name "unconnected-(U4-SD2-Pad17)") (class "Default")
      (node (ref "U4") (pin "17") (pinfunction "SD2_17") (pintype "bidirectional"))
    )
    (net (code "84") (name "unconnected-(U4-SD3-Pad18)") (class "Default")
      (node (ref "U4") (pin "18") (pinfunction "SD3_18") (pintype "bidirectional"))
    )
    (net (code "85") (name "unconnected-(U4-SDO-Pad21)") (class "Default")
      (node (ref "U4") (pin "21") (pinfunction "SDO_21") (pintype "bidirectional"))
    )
    (net (code "86") (name "unconnected-(U4-SENSOR_VN-Pad5)") (class "Default")
      (node (ref "U4") (pin "5") (pinfunction "SENSOR_VN_5") (pintype "input"))
    )
    (net (code "87") (name "unconnected-(U4-SENSOR_VP-Pad4)") (class "Default")
      (node (ref "U4") (pin "4") (pinfunction "SENSOR_VP_4") (pintype "input"))
    )
  )
)
